# HEALA.net
KiCad netlist of a schematic drawn in Altium Designer
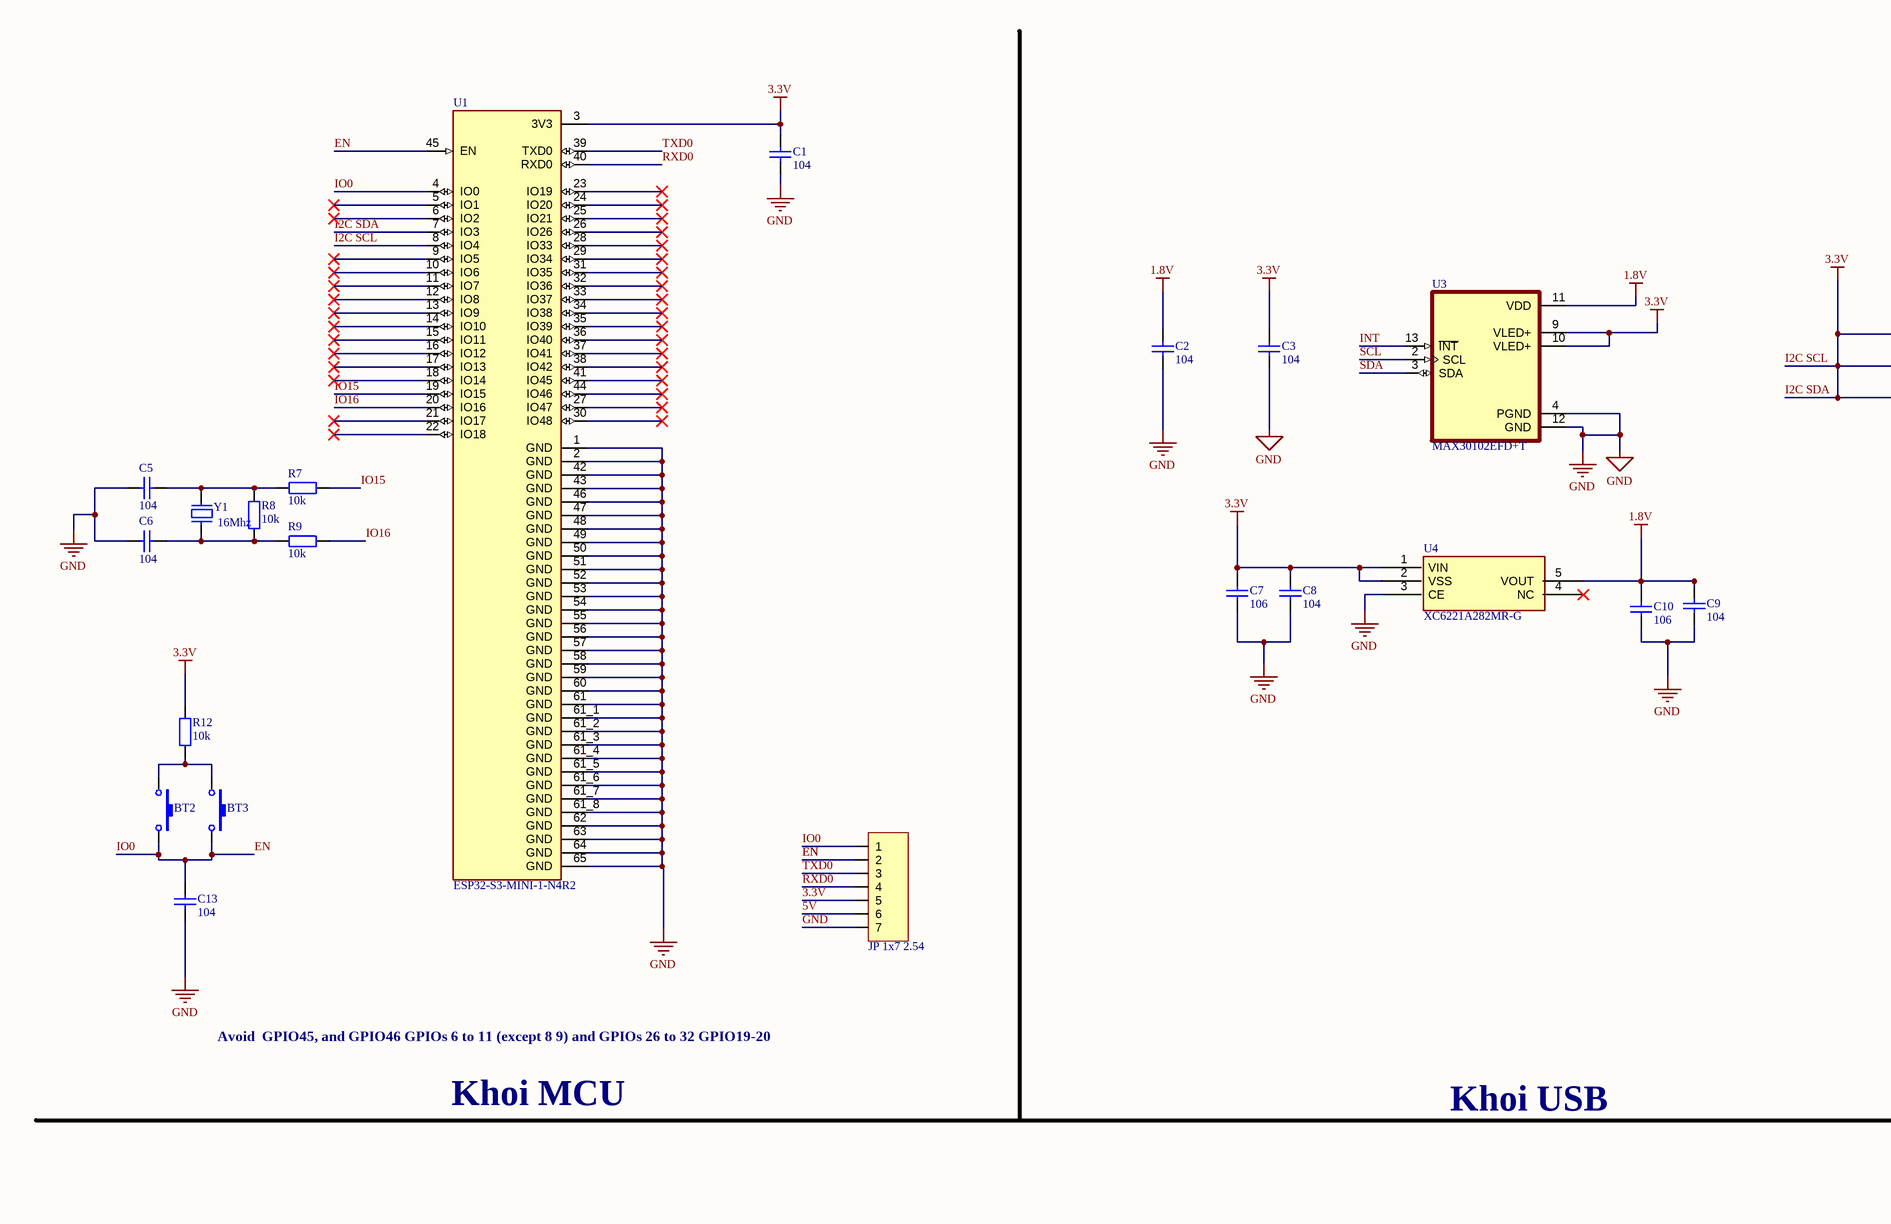
[diagram p0: HEALA.SchDoc, left]
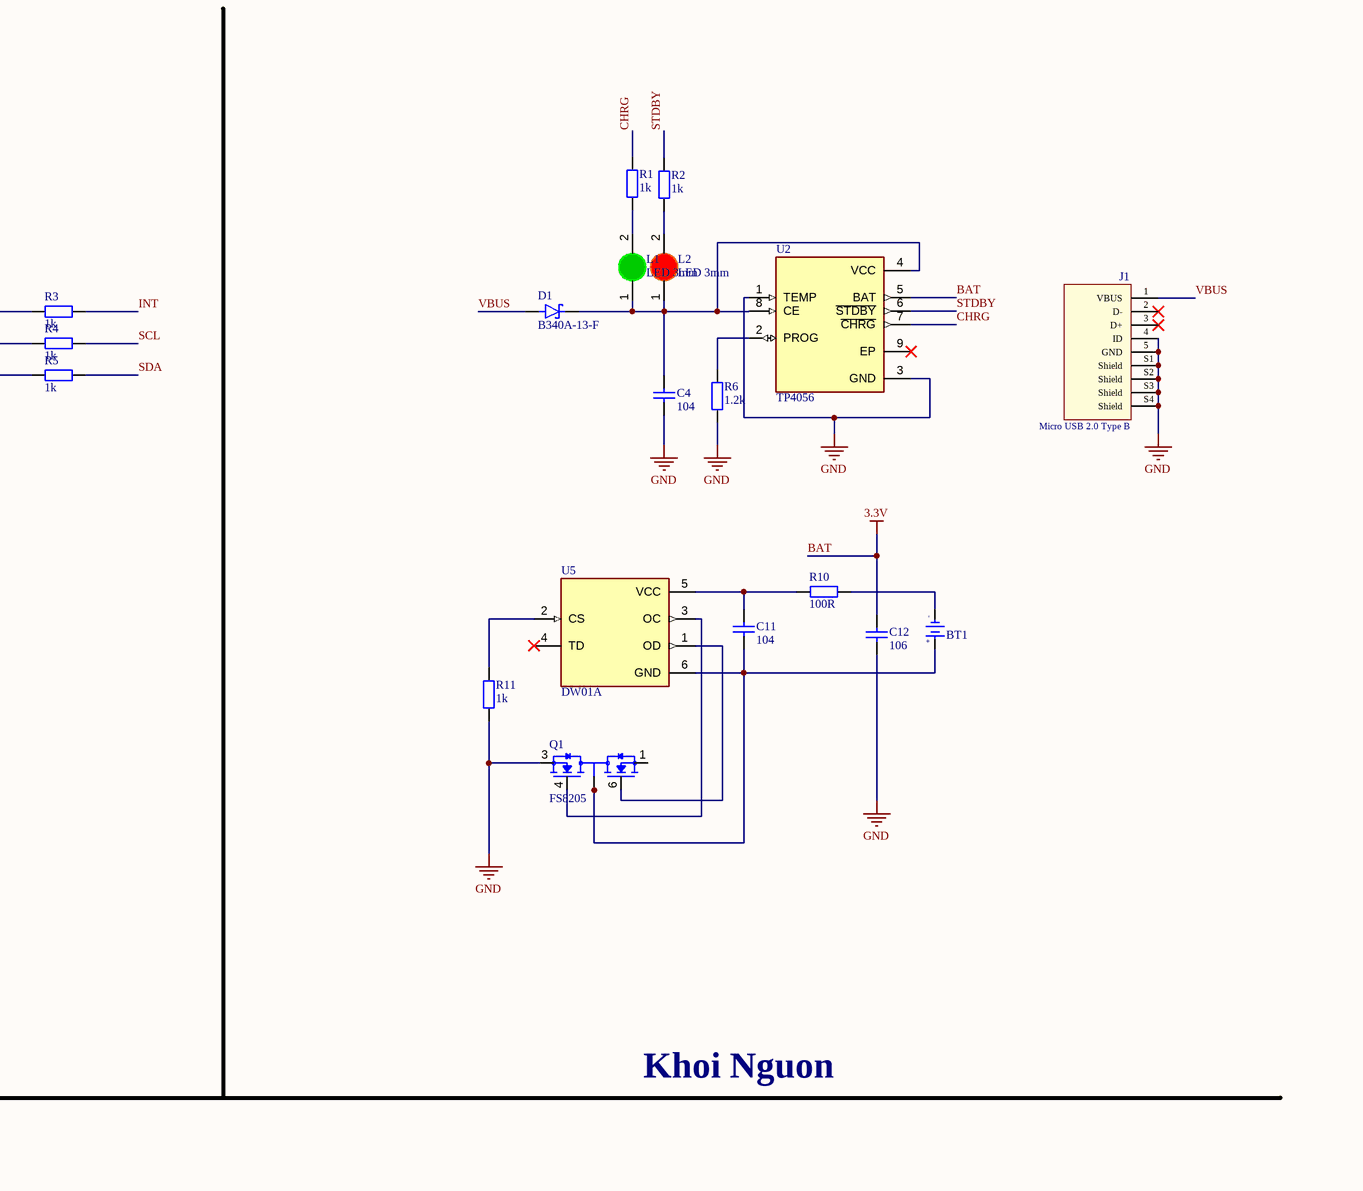
[diagram p1: HEALA.SchDoc, right]

(export (version "E")
  (design (tool "Eeschema 10.0.6"))
  (components
    (comp (ref "BT1")
      (value "NI-MH 3.6V 20mAh 3/V20H")
      (footprint "PIN 3.6V 20mAh 3/V20H")
      (description "Battery 3VDC , NI-MH 3.6V 20mAh 3/V20H")
      (libsource (lib "Component") (part "PIN 3V"))
    )
    (comp (ref "BT2")
      (value "Nut Nhan 2 Chan SMD 3x6x2.5")
      (footprint "Nut Nhan 2 Chan SMD 3x6x2.5")
      (libsource (lib "Component") (part "Nut Nhan 2 Chan SMD 3x6x2.5"))
    )
    (comp (ref "BT3")
      (value "Nut Nhan 2 Chan SMD 3x6x2.5")
      (footprint "Nut Nhan 2 Chan SMD 3x6x2.5")
      (libsource (lib "Component") (part "Nut Nhan 2 Chan SMD 3x6x2.5"))
    )
    (comp (ref "C1")
      (value "104")
      (footprint "tu 1206")
      (description "Dán")
      (libsource (lib "Capacitor") (part "Tu 1206 104 50V 20%"))
    )
    (comp (ref "C2")
      (value "104")
      (footprint "tu 1206")
      (description "Dán")
      (libsource (lib "Capacitor") (part "Tu 1206 104 50V 20%"))
    )
    (comp (ref "C3")
      (value "104")
      (footprint "tu 1206")
      (description "Dán")
      (libsource (lib "Capacitor") (part "Tu 1206 104 50V 20%"))
    )
    (comp (ref "C4")
      (value "104")
      (footprint "tu 0805")
      (description "Dán")
      (libsource (lib "Capacitor") (part "Tu 0805 104 50V 10%"))
    )
    (comp (ref "C5")
      (value "104")
      (footprint "tu 1206")
      (description "Dán")
      (libsource (lib "Capacitor") (part "Tu 1206 104 50V 20%"))
    )
    (comp (ref "C6")
      (value "104")
      (footprint "tu 1206")
      (description "Dán")
      (libsource (lib "Capacitor") (part "Tu 1206 104 50V 20%"))
    )
    (comp (ref "C7")
      (value "106")
      (footprint "tu 1206")
      (description "Dán")
      (libsource (lib "Capacitor") (part "Tu 1206 106 16V 20%"))
    )
    (comp (ref "C8")
      (value "104")
      (footprint "tu 1206")
      (description "Dán")
      (libsource (lib "Capacitor") (part "Tu 1206 104 50V 20%"))
    )
    (comp (ref "C9")
      (value "104")
      (footprint "tu 1206")
      (description "Dán")
      (libsource (lib "Capacitor") (part "Tu 1206 104 50V 20%"))
    )
    (comp (ref "C10")
      (value "106")
      (footprint "tu 1206")
      (description "Dán")
      (libsource (lib "Capacitor") (part "Tu 1206 106 16V 20%"))
    )
    (comp (ref "C11")
      (value "104")
      (footprint "tu 1206")
      (description "Dán")
      (libsource (lib "Capacitor") (part "Tu 1206 104 50V 20%"))
    )
    (comp (ref "C12")
      (value "106")
      (footprint "tu 1206")
      (description "Dán")
      (libsource (lib "Capacitor") (part "Tu 1206 106 16V 20%"))
    )
    (comp (ref "C13")
      (value "104")
      (footprint "tu 1206")
      (description "Dán")
      (libsource (lib "Capacitor") (part "Tu 1206 104 50V 20%"))
    )
    (comp (ref "D1")
      (value "B340A-13-F")
      (footprint "DIOM5226X240N")
      (description "Diode Schottky 40V 3A Surface Mount SMA")
      (fields (field (name "MF") "Diodes Inc."))
      (libsource (lib "Diode") (part "B340A-13-F"))
    )
    (comp (ref "J1")
      (value "Micro USB 2.0 Type B")
      (footprint "629105136821")
      (description "Micro USB 2.0 Type B Horizontal SMT 5 Contacts WR-COM")
      (fields (field (name "PART NUMBER") "629105136821") (field (name "PUBLISHER") "Wurth Elektronik"))
      (libsource (lib "USB") (part "629105136821"))
    )
    (comp (ref "JP1")
      (value "JP 1x7 2.54")
      (footprint "JP 1x7 CT")
      (description "Cắm")
      (libsource (lib "Jump") (part "JP 1x7 2.54 Cai Thang"))
    )
    (comp (ref "L1")
      (value "LED 3mm")
      (footprint "LED-3MM-GREEN")
      (description "Cắm")
      (libsource (lib "Led") (part "LED 3mm Xanh La"))
    )
    (comp (ref "L2")
      (value "LED 3mm")
      (footprint "LED-3MM-RED")
      (description "Cắm")
      (libsource (lib "Led") (part "LED 3mm Do"))
    )
    (comp (ref "Q1")
      (value "FS8205")
      (footprint "SOT95P280X145-6N")
      (fields (field (name "MF") "Fortune Semiconductor"))
      (libsource (lib "FS8205") (part "FS8205"))
    )
    (comp (ref "R1")
      (value "1k")
      (footprint "tro smd 0603")
      (description "Dán")
      (libsource (lib "Resistor") (part "Tro 0603 1% 1k"))
    )
    (comp (ref "R2")
      (value "1k")
      (footprint "tro smd 0603")
      (description "Dán")
      (libsource (lib "Resistor") (part "Tro 0603 1% 1k"))
    )
    (comp (ref "R3")
      (value "1k")
      (footprint "tro smd 1206")
      (description "Dán")
      (libsource (lib "Resistor") (part "Tro 1206 5% 1k"))
    )
    (comp (ref "R4")
      (value "1k")
      (footprint "tro smd 1206")
      (description "Dán")
      (libsource (lib "Resistor") (part "Tro 1206 5% 1k"))
    )
    (comp (ref "R5")
      (value "1k")
      (footprint "tro smd 1206")
      (description "Dán")
      (libsource (lib "Resistor") (part "Tro 1206 5% 1k"))
    )
    (comp (ref "R6")
      (value "1.2k")
      (footprint "tro smd 1206")
      (description "Dán")
      (libsource (lib "Resistor") (part "Tro 1206 5% 1.2k"))
    )
    (comp (ref "R7")
      (value "10k")
      (footprint "tro smd 1206")
      (description "Dán")
      (libsource (lib "Resistor") (part "Tro 1206 5% 10k"))
    )
    (comp (ref "R8")
      (value "10k")
      (footprint "tro smd 1206")
      (description "Dán")
      (libsource (lib "Resistor") (part "Tro 1206 5% 10k"))
    )
    (comp (ref "R9")
      (value "10k")
      (footprint "tro smd 1206")
      (description "Dán")
      (libsource (lib "Resistor") (part "Tro 1206 5% 10k"))
    )
    (comp (ref "R10")
      (value "100R")
      (footprint "tro smd 1206")
      (description "Dán")
      (libsource (lib "Resistor") (part "Tro 1206 1% 100R"))
    )
    (comp (ref "R11")
      (value "1k")
      (footprint "tro smd 1206")
      (description "Dán")
      (libsource (lib "Resistor") (part "Tro 1206 5% 1k"))
    )
    (comp (ref "R12")
      (value "10k")
      (footprint "tro smd 1206")
      (description "Dán")
      (libsource (lib "Resistor") (part "Tro 1206 5% 10k"))
    )
    (comp (ref "U1")
      (value "ESP32-S3-MINI-1-N4R2")
      (footprint "XCVR_ESP32-S3-MINI-1-N4R2")
      (description "Bluetooth, WiFi 802.11b/g/n, Bluetooth v5.0 Transceiver Module 2.4GHz PCB Trace Surface Mount")
      (fields (field (name "MF") "Espressif Systems"))
      (libsource (lib "HEALA") (part "ESP32-S3-MINI-1-N4R2"))
    )
    (comp (ref "U2")
      (value "TP4056")
      (footprint "SOP127P600X175-9N")
      (description "Complete single cell Li-Ion battery with a constant current / constant voltage linear charger")
      (fields (field (name "MF") "NanJing Top Power ASIC Corp."))
      (libsource (lib "HEALA") (part "TP4056"))
    )
    (comp (ref "U3")
      (value "MAX30102EFD+T")
      (footprint "XDCR_MAX30101EFD+")
      (description "Pulse Oximeter and Heart Rate Sensor Digital Output")
      (fields
        (field (name "DIGI-KEY_PART_NUMBER") "MAX30102EFD+TTR-ND")
        (field (name "MF") "Maxim Integrated Products")
      )
      (libsource (lib "HEALA") (part "MAX30102EFD+T"))
    )
    (comp (ref "U4")
      (value "XC6221A282MR-G")
      (footprint "SOT95P280X120-5N")
      (libsource (lib "HEALA") (part "XC6221A282MR-G"))
    )
    (comp (ref "U5")
      (value "DW01A")
      (footprint "SOT95P280X145-6N")
      (description "One Cell Lithium-ion/Polymer Battery Protection IC")
      (fields (field (name "MF") "Fortune Semiconductor"))
      (libsource (lib "DW01A") (part "DW01A"))
    )
    (comp (ref "Y1")
      (value "16Mhz")
      (footprint "Thach Anh 2 Chan 32,768 KHz")
      (description "Crystal For all Crystal 2pin.")
      (libsource (lib "Component") (part "Thach Anh 2 chan 32,768 Khz"))
    )
  )
  (nets
    (net (code "1") (name "/5V") (class "Default")
      (node (ref "JP1") (pin "6") (pinfunction "6_6") (pintype "passive"))
    )
    (net (code "2") (name "/CHRG") (class "Default")
      (node (ref "R1") (pin "2") (pinfunction "2_2") (pintype "passive"))
      (node (ref "U2") (pin "7") (pinfunction "~{CHRG}_7") (pintype "output"))
    )
    (net (code "3") (name "/EN") (class "Default")
      (node (ref "BT2") (pin "2") (pinfunction "2_2") (pintype "passive"))
      (node (ref "BT3") (pin "2") (pinfunction "2_2") (pintype "passive"))
      (node (ref "C13") (pin "1") (pinfunction "1_1") (pintype "passive"))
      (node (ref "JP1") (pin "1") (pinfunction "1_1") (pintype "passive"))
      (node (ref "JP1") (pin "2") (pinfunction "2_2") (pintype "passive"))
      (node (ref "U1") (pin "4") (pinfunction "IO0_4") (pintype "bidirectional"))
      (node (ref "U1") (pin "45") (pinfunction "EN_45") (pintype "input"))
    )
    (net (code "4") (name "/INT") (class "Default")
      (node (ref "R3") (pin "2") (pinfunction "2_2") (pintype "passive"))
      (node (ref "U3") (pin "13") (pinfunction "~{INT}_13") (pintype "input"))
    )
    (net (code "5") (name "/IO15") (class "Default")
      (node (ref "R7") (pin "2") (pinfunction "2_2") (pintype "passive"))
      (node (ref "U1") (pin "19") (pinfunction "IO15_19") (pintype "bidirectional"))
    )
    (net (code "6") (name "/IO16") (class "Default")
      (node (ref "R9") (pin "2") (pinfunction "2_2") (pintype "passive"))
      (node (ref "U1") (pin "20") (pinfunction "IO16_20") (pintype "bidirectional"))
    )
    (net (code "7") (name "/RXD0") (class "Default")
      (node (ref "JP1") (pin "4") (pinfunction "4_4") (pintype "passive"))
      (node (ref "U1") (pin "40") (pinfunction "RXD0_40") (pintype "bidirectional"))
    )
    (net (code "8") (name "/SCL") (class "Default")
      (node (ref "R4") (pin "2") (pinfunction "2_2") (pintype "passive"))
      (node (ref "U3") (pin "2") (pinfunction "SCL_2") (pintype "input"))
    )
    (net (code "9") (name "/SDA") (class "Default")
      (node (ref "R5") (pin "2") (pinfunction "2_2") (pintype "passive"))
      (node (ref "U3") (pin "3") (pinfunction "SDA_3") (pintype "bidirectional"))
    )
    (net (code "10") (name "/STDBY") (class "Default")
      (node (ref "R2") (pin "2") (pinfunction "2_2") (pintype "passive"))
      (node (ref "U2") (pin "6") (pinfunction "~{STDBY}_6") (pintype "output"))
    )
    (net (code "11") (name "/TXD0") (class "Default")
      (node (ref "JP1") (pin "3") (pinfunction "3_3") (pintype "passive"))
      (node (ref "U1") (pin "39") (pinfunction "TXD0_39") (pintype "bidirectional"))
    )
    (net (code "12") (name "/VBUS") (class "Default")
      (node (ref "D1") (pin "A") (pinfunction "A_A") (pintype "passive"))
      (node (ref "J1") (pin "1") (pinfunction "VBUS_1") (pintype "passive"))
    )
    (net (code "13") (name "1.8V") (class "Default")
      (node (ref "C2") (pin "1") (pinfunction "1_1") (pintype "passive"))
      (node (ref "U3") (pin "11") (pinfunction "VDD_11") (pintype "power_in"))
    )
    (net (code "14") (name "3.3V") (class "Default")
      (node (ref "C1") (pin "1") (pinfunction "1_1") (pintype "passive"))
      (node (ref "C12") (pin "1") (pinfunction "1_1") (pintype "passive"))
      (node (ref "C3") (pin "1") (pinfunction "1_1") (pintype "passive"))
      (node (ref "C7") (pin "1") (pinfunction "1_1") (pintype "passive"))
      (node (ref "C8") (pin "1") (pinfunction "1_1") (pintype "passive"))
      (node (ref "JP1") (pin "5") (pinfunction "5_5") (pintype "passive"))
      (node (ref "R12") (pin "2") (pinfunction "2_2") (pintype "passive"))
      (node (ref "R3") (pin "1") (pinfunction "1_1") (pintype "passive"))
      (node (ref "R4") (pin "1") (pinfunction "1_1") (pintype "passive"))
      (node (ref "R5") (pin "1") (pinfunction "1_1") (pintype "passive"))
      (node (ref "U1") (pin "3") (pinfunction "3V3_3") (pintype "power_in"))
      (node (ref "U1") (pin "7") (pinfunction "IO3_7") (pintype "bidirectional"))
      (node (ref "U1") (pin "8") (pinfunction "IO4_8") (pintype "bidirectional"))
      (node (ref "U2") (pin "5") (pinfunction "BAT_5") (pintype "output"))
      (node (ref "U3") (pin "10") (pinfunction "VLED+_10") (pintype "power_in"))
      (node (ref "U3") (pin "9") (pinfunction "VLED+_9") (pintype "power_in"))
      (node (ref "U4") (pin "1") (pinfunction "VIN_1") (pintype "passive"))
      (node (ref "U4") (pin "2") (pinfunction "VSS_2") (pintype "passive"))
    )
    (net (code "15") (name "GND") (class "Default")
      (node (ref "C1") (pin "2") (pinfunction "2_2") (pintype "passive"))
      (node (ref "C10") (pin "2") (pinfunction "2_2") (pintype "passive"))
      (node (ref "C12") (pin "2") (pinfunction "2_2") (pintype "passive"))
      (node (ref "C13") (pin "2") (pinfunction "2_2") (pintype "passive"))
      (node (ref "C2") (pin "2") (pinfunction "2_2") (pintype "passive"))
      (node (ref "C3") (pin "2") (pinfunction "2_2") (pintype "passive"))
      (node (ref "C4") (pin "2") (pinfunction "2_2") (pintype "passive"))
      (node (ref "C5") (pin "2") (pinfunction "2_2") (pintype "passive"))
      (node (ref "C6") (pin "2") (pinfunction "2_2") (pintype "passive"))
      (node (ref "C7") (pin "2") (pinfunction "2_2") (pintype "passive"))
      (node (ref "C8") (pin "2") (pinfunction "2_2") (pintype "passive"))
      (node (ref "C9") (pin "2") (pinfunction "2_2") (pintype "passive"))
      (node (ref "J1") (pin "4") (pinfunction "ID_4") (pintype "passive"))
      (node (ref "J1") (pin "5") (pinfunction "GND_5") (pintype "passive"))
      (node (ref "J1") (pin "S1") (pinfunction "Shield_S1") (pintype "passive"))
      (node (ref "J1") (pin "S2") (pinfunction "Shield_S2") (pintype "passive"))
      (node (ref "J1") (pin "S3") (pinfunction "Shield_S3") (pintype "passive"))
      (node (ref "J1") (pin "S4") (pinfunction "Shield_S4") (pintype "passive"))
      (node (ref "JP1") (pin "7") (pinfunction "7_7") (pintype "passive"))
      (node (ref "Q1") (pin "3") (pinfunction "S2_3") (pintype "passive"))
      (node (ref "R11") (pin "1") (pinfunction "1_1") (pintype "passive"))
      (node (ref "R6") (pin "1") (pinfunction "1_1") (pintype "passive"))
      (node (ref "U1") (pin "1") (pinfunction "GND_1") (pintype "power_in"))
      (node (ref "U1") (pin "2") (pinfunction "GND_2") (pintype "power_in"))
      (node (ref "U1") (pin "42") (pinfunction "GND_42") (pintype "power_in"))
      (node (ref "U1") (pin "43") (pinfunction "GND_43") (pintype "power_in"))
      (node (ref "U1") (pin "46") (pinfunction "GND_46") (pintype "power_in"))
      (node (ref "U1") (pin "47") (pinfunction "GND_47") (pintype "power_in"))
      (node (ref "U1") (pin "48") (pinfunction "GND_48") (pintype "power_in"))
      (node (ref "U1") (pin "49") (pinfunction "GND_49") (pintype "power_in"))
      (node (ref "U1") (pin "50") (pinfunction "GND_50") (pintype "power_in"))
      (node (ref "U1") (pin "51") (pinfunction "GND_51") (pintype "power_in"))
      (node (ref "U1") (pin "52") (pinfunction "GND_52") (pintype "power_in"))
      (node (ref "U1") (pin "53") (pinfunction "GND_53") (pintype "power_in"))
      (node (ref "U1") (pin "54") (pinfunction "GND_54") (pintype "power_in"))
      (node (ref "U1") (pin "55") (pinfunction "GND_55") (pintype "power_in"))
      (node (ref "U1") (pin "56") (pinfunction "GND_56") (pintype "power_in"))
      (node (ref "U1") (pin "57") (pinfunction "GND_57") (pintype "power_in"))
      (node (ref "U1") (pin "58") (pinfunction "GND_58") (pintype "power_in"))
      (node (ref "U1") (pin "59") (pinfunction "GND_59") (pintype "power_in"))
      (node (ref "U1") (pin "60") (pinfunction "GND_60") (pintype "power_in"))
      (node (ref "U1") (pin "61") (pinfunction "GND_61") (pintype "power_in"))
      (node (ref "U1") (pin "61_1") (pinfunction "GND_61_1") (pintype "power_in"))
      (node (ref "U1") (pin "61_2") (pinfunction "GND_61_2") (pintype "power_in"))
      (node (ref "U1") (pin "61_3") (pinfunction "GND_61_3") (pintype "power_in"))
      (node (ref "U1") (pin "61_4") (pinfunction "GND_61_4") (pintype "power_in"))
      (node (ref "U1") (pin "61_5") (pinfunction "GND_61_5") (pintype "power_in"))
      (node (ref "U1") (pin "61_6") (pinfunction "GND_61_6") (pintype "power_in"))
      (node (ref "U1") (pin "61_7") (pinfunction "GND_61_7") (pintype "power_in"))
      (node (ref "U1") (pin "61_8") (pinfunction "GND_61_8") (pintype "power_in"))
      (node (ref "U1") (pin "62") (pinfunction "GND_62") (pintype "power_in"))
      (node (ref "U1") (pin "63") (pinfunction "GND_63") (pintype "power_in"))
      (node (ref "U1") (pin "64") (pinfunction "GND_64") (pintype "power_in"))
      (node (ref "U1") (pin "65") (pinfunction "GND_65") (pintype "power_in"))
      (node (ref "U2") (pin "1") (pinfunction "TEMP_1") (pintype "input"))
      (node (ref "U2") (pin "3") (pinfunction "GND_3") (pintype "power_in"))
      (node (ref "U3") (pin "12") (pinfunction "GND_12") (pintype "power_in"))
      (node (ref "U3") (pin "4") (pinfunction "PGND_4") (pintype "power_in"))
      (node (ref "U4") (pin "3") (pinfunction "CE_3") (pintype "passive"))
    )
    (net (code "16") (name "Net-(BT1-+3V)") (class "Default")
      (node (ref "BT1") (pin "1") (pinfunction "+3V_1") (pintype "passive"))
      (node (ref "C11") (pin "2") (pinfunction "2_2") (pintype "passive"))
      (node (ref "Q1") (pin "2") (pinfunction "D12_2") (pintype "passive"))
      (node (ref "Q1") (pin "5") (pinfunction "D12_5") (pintype "passive"))
      (node (ref "U5") (pin "6") (pinfunction "GND_6") (pintype "power_in"))
    )
    (net (code "17") (name "Net-(BT1-GND)") (class "Default")
      (node (ref "BT1") (pin "2") (pinfunction "GND_2") (pintype "passive"))
      (node (ref "R10") (pin "2") (pinfunction "2_2") (pintype "passive"))
    )
    (net (code "18") (name "Net-(BT2-Pad1)") (class "Default")
      (node (ref "BT2") (pin "1") (pinfunction "1_1") (pintype "passive"))
      (node (ref "BT3") (pin "1") (pinfunction "1_1") (pintype "passive"))
      (node (ref "R12") (pin "1") (pinfunction "1_1") (pintype "passive"))
    )
    (net (code "19") (name "Net-(C5-Pad1)") (class "Default")
      (node (ref "C5") (pin "1") (pinfunction "1_1") (pintype "passive"))
      (node (ref "R7") (pin "1") (pinfunction "1_1") (pintype "passive"))
      (node (ref "R8") (pin "2") (pinfunction "2_2") (pintype "passive"))
      (node (ref "Y1") (pin "2") (pinfunction "2_2") (pintype "passive"))
    )
    (net (code "20") (name "Net-(C6-Pad1)") (class "Default")
      (node (ref "C6") (pin "1") (pinfunction "1_1") (pintype "passive"))
      (node (ref "R8") (pin "1") (pinfunction "1_1") (pintype "passive"))
      (node (ref "R9") (pin "1") (pinfunction "1_1") (pintype "passive"))
      (node (ref "Y1") (pin "1") (pinfunction "1_1") (pintype "passive"))
    )
    (net (code "21") (name "Net-(L1-A)") (class "Default")
      (node (ref "C4") (pin "1") (pinfunction "1_1") (pintype "passive"))
      (node (ref "D1") (pin "C") (pinfunction "C_C") (pintype "passive"))
      (node (ref "L1") (pin "1") (pinfunction "A_1") (pintype "passive"))
      (node (ref "L2") (pin "1") (pinfunction "A_1") (pintype "passive"))
      (node (ref "U2") (pin "4") (pinfunction "VCC_4") (pintype "power_in"))
      (node (ref "U2") (pin "8") (pinfunction "CE_8") (pintype "input"))
    )
    (net (code "22") (name "Net-(L1-K)") (class "Default")
      (node (ref "L1") (pin "2") (pinfunction "K_2") (pintype "passive"))
      (node (ref "R1") (pin "1") (pinfunction "1_1") (pintype "passive"))
    )
    (net (code "23") (name "Net-(L2-K)") (class "Default")
      (node (ref "L2") (pin "2") (pinfunction "K_2") (pintype "passive"))
      (node (ref "R2") (pin "1") (pinfunction "1_1") (pintype "passive"))
    )
    (net (code "24") (name "Net-(Q1-G1)") (class "Default")
      (node (ref "Q1") (pin "6") (pinfunction "G1_6") (pintype "passive"))
      (node (ref "U5") (pin "1") (pinfunction "OD_1") (pintype "output"))
    )
    (net (code "25") (name "Net-(Q1-G2)") (class "Default")
      (node (ref "Q1") (pin "4") (pinfunction "G2_4") (pintype "passive"))
      (node (ref "U5") (pin "3") (pinfunction "OC_3") (pintype "output"))
    )
    (net (code "26") (name "Net-(U2-PROG)") (class "Default")
      (node (ref "R6") (pin "2") (pinfunction "2_2") (pintype "passive"))
      (node (ref "U2") (pin "2") (pinfunction "PROG_2") (pintype "bidirectional"))
    )
    (net (code "27") (name "Net-(U4-VOUT)") (class "Default")
      (node (ref "C10") (pin "1") (pinfunction "1_1") (pintype "passive"))
      (node (ref "C9") (pin "1") (pinfunction "1_1") (pintype "passive"))
      (node (ref "U4") (pin "5") (pinfunction "VOUT_5") (pintype "passive"))
    )
    (net (code "28") (name "Net-(U5-CS)") (class "Default")
      (node (ref "R11") (pin "2") (pinfunction "2_2") (pintype "passive"))
      (node (ref "U5") (pin "2") (pinfunction "CS_2") (pintype "input"))
    )
    (net (code "29") (name "Net-(U5-VCC)") (class "Default")
      (node (ref "C11") (pin "1") (pinfunction "1_1") (pintype "passive"))
      (node (ref "R10") (pin "1") (pinfunction "1_1") (pintype "passive"))
      (node (ref "U5") (pin "5") (pinfunction "VCC_5") (pintype "power_in"))
    )
    (net (code "30") (name "unconnected-(J1-D+-Pad3)") (class "Default")
      (node (ref "J1") (pin "3") (pinfunction "D+_3") (pintype "passive+no_connect"))
    )
    (net (code "31") (name "unconnected-(J1-D--Pad2)") (class "Default")
      (node (ref "J1") (pin "2") (pinfunction "D-_2") (pintype "passive+no_connect"))
    )
    (net (code "32") (name "unconnected-(Q1-S1-Pad1)") (class "Default")
      (node (ref "Q1") (pin "1") (pinfunction "S1_1") (pintype "passive"))
    )
    (net (code "33") (name "unconnected-(U1-IO1-Pad5)") (class "Default")
      (node (ref "U1") (pin "5") (pinfunction "IO1_5") (pintype "bidirectional+no_connect"))
    )
    (net (code "34") (name "unconnected-(U1-IO2-Pad6)") (class "Default")
      (node (ref "U1") (pin "6") (pinfunction "IO2_6") (pintype "bidirectional+no_connect"))
    )
    (net (code "35") (name "unconnected-(U1-IO5-Pad9)") (class "Default")
      (node (ref "U1") (pin "9") (pinfunction "IO5_9") (pintype "bidirectional+no_connect"))
    )
    (net (code "36") (name "unconnected-(U1-IO6-Pad10)") (class "Default")
      (node (ref "U1") (pin "10") (pinfunction "IO6_10") (pintype "bidirectional+no_connect"))
    )
    (net (code "37") (name "unconnected-(U1-IO7-Pad11)") (class "Default")
      (node (ref "U1") (pin "11") (pinfunction "IO7_11") (pintype "bidirectional+no_connect"))
    )
    (net (code "38") (name "unconnected-(U1-IO8-Pad12)") (class "Default")
      (node (ref "U1") (pin "12") (pinfunction "IO8_12") (pintype "bidirectional+no_connect"))
    )
    (net (code "39") (name "unconnected-(U1-IO9-Pad13)") (class "Default")
      (node (ref "U1") (pin "13") (pinfunction "IO9_13") (pintype "bidirectional+no_connect"))
    )
    (net (code "40") (name "unconnected-(U1-IO10-Pad14)") (class "Default")
      (node (ref "U1") (pin "14") (pinfunction "IO10_14") (pintype "bidirectional+no_connect"))
    )
    (net (code "41") (name "unconnected-(U1-IO11-Pad15)") (class "Default")
      (node (ref "U1") (pin "15") (pinfunction "IO11_15") (pintype "bidirectional+no_connect"))
    )
    (net (code "42") (name "unconnected-(U1-IO12-Pad16)") (class "Default")
      (node (ref "U1") (pin "16") (pinfunction "IO12_16") (pintype "bidirectional+no_connect"))
    )
    (net (code "43") (name "unconnected-(U1-IO13-Pad17)") (class "Default")
      (node (ref "U1") (pin "17") (pinfunction "IO13_17") (pintype "bidirectional+no_connect"))
    )
    (net (code "44") (name "unconnected-(U1-IO14-Pad18)") (class "Default")
      (node (ref "U1") (pin "18") (pinfunction "IO14_18") (pintype "bidirectional+no_connect"))
    )
    (net (code "45") (name "unconnected-(U1-IO17-Pad21)") (class "Default")
      (node (ref "U1") (pin "21") (pinfunction "IO17_21") (pintype "bidirectional+no_connect"))
    )
    (net (code "46") (name "unconnected-(U1-IO18-Pad22)") (class "Default")
      (node (ref "U1") (pin "22") (pinfunction "IO18_22") (pintype "bidirectional+no_connect"))
    )
    (net (code "47") (name "unconnected-(U1-IO19-Pad23)") (class "Default")
      (node (ref "U1") (pin "23") (pinfunction "IO19_23") (pintype "bidirectional+no_connect"))
    )
    (net (code "48") (name "unconnected-(U1-IO20-Pad24)") (class "Default")
      (node (ref "U1") (pin "24") (pinfunction "IO20_24") (pintype "bidirectional+no_connect"))
    )
    (net (code "49") (name "unconnected-(U1-IO21-Pad25)") (class "Default")
      (node (ref "U1") (pin "25") (pinfunction "IO21_25") (pintype "bidirectional+no_connect"))
    )
    (net (code "50") (name "unconnected-(U1-IO26-Pad26)") (class "Default")
      (node (ref "U1") (pin "26") (pinfunction "IO26_26") (pintype "bidirectional+no_connect"))
    )
    (net (code "51") (name "unconnected-(U1-IO33-Pad28)") (class "Default")
      (node (ref "U1") (pin "28") (pinfunction "IO33_28") (pintype "bidirectional+no_connect"))
    )
    (net (code "52") (name "unconnected-(U1-IO34-Pad29)") (class "Default")
      (node (ref "U1") (pin "29") (pinfunction "IO34_29") (pintype "bidirectional+no_connect"))
    )
    (net (code "53") (name "unconnected-(U1-IO35-Pad31)") (class "Default")
      (node (ref "U1") (pin "31") (pinfunction "IO35_31") (pintype "bidirectional+no_connect"))
    )
    (net (code "54") (name "unconnected-(U1-IO36-Pad32)") (class "Default")
      (node (ref "U1") (pin "32") (pinfunction "IO36_32") (pintype "bidirectional+no_connect"))
    )
    (net (code "55") (name "unconnected-(U1-IO37-Pad33)") (class "Default")
      (node (ref "U1") (pin "33") (pinfunction "IO37_33") (pintype "bidirectional+no_connect"))
    )
    (net (code "56") (name "unconnected-(U1-IO38-Pad34)") (class "Default")
      (node (ref "U1") (pin "34") (pinfunction "IO38_34") (pintype "bidirectional+no_connect"))
    )
    (net (code "57") (name "unconnected-(U1-IO39-Pad35)") (class "Default")
      (node (ref "U1") (pin "35") (pinfunction "IO39_35") (pintype "bidirectional+no_connect"))
    )
    (net (code "58") (name "unconnected-(U1-IO40-Pad36)") (class "Default")
      (node (ref "U1") (pin "36") (pinfunction "IO40_36") (pintype "bidirectional+no_connect"))
    )
    (net (code "59") (name "unconnected-(U1-IO41-Pad37)") (class "Default")
      (node (ref "U1") (pin "37") (pinfunction "IO41_37") (pintype "bidirectional+no_connect"))
    )
    (net (code "60") (name "unconnected-(U1-IO42-Pad38)") (class "Default")
      (node (ref "U1") (pin "38") (pinfunction "IO42_38") (pintype "bidirectional+no_connect"))
    )
    (net (code "61") (name "unconnected-(U1-IO45-Pad41)") (class "Default")
      (node (ref "U1") (pin "41") (pinfunction "IO45_41") (pintype "bidirectional+no_connect"))
    )
    (net (code "62") (name "unconnected-(U1-IO46-Pad44)") (class "Default")
      (node (ref "U1") (pin "44") (pinfunction "IO46_44") (pintype "bidirectional+no_connect"))
    )
    (net (code "63") (name "unconnected-(U1-IO47-Pad27)") (class "Default")
      (node (ref "U1") (pin "27") (pinfunction "IO47_27") (pintype "bidirectional+no_connect"))
    )
    (net (code "64") (name "unconnected-(U1-IO48-Pad30)") (class "Default")
      (node (ref "U1") (pin "30") (pinfunction "IO48_30") (pintype "bidirectional+no_connect"))
    )
    (net (code "65") (name "unconnected-(U2-EP-Pad9)") (class "Default")
      (node (ref "U2") (pin "9") (pinfunction "EP_9") (pintype "passive+no_connect"))
    )
    (net (code "66") (name "unconnected-(U4-NC-Pad4)") (class "Default")
      (node (ref "U4") (pin "4") (pinfunction "NC_4") (pintype "passive+no_connect"))
    )
    (net (code "67") (name "unconnected-(U5-TD-Pad4)") (class "Default")
      (node (ref "U5") (pin "4") (pinfunction "TD_4") (pintype "passive+no_connect"))
    )
  )
)
